# RTI-RoR.net
KiCad netlist of a schematic drawn in EAGLE
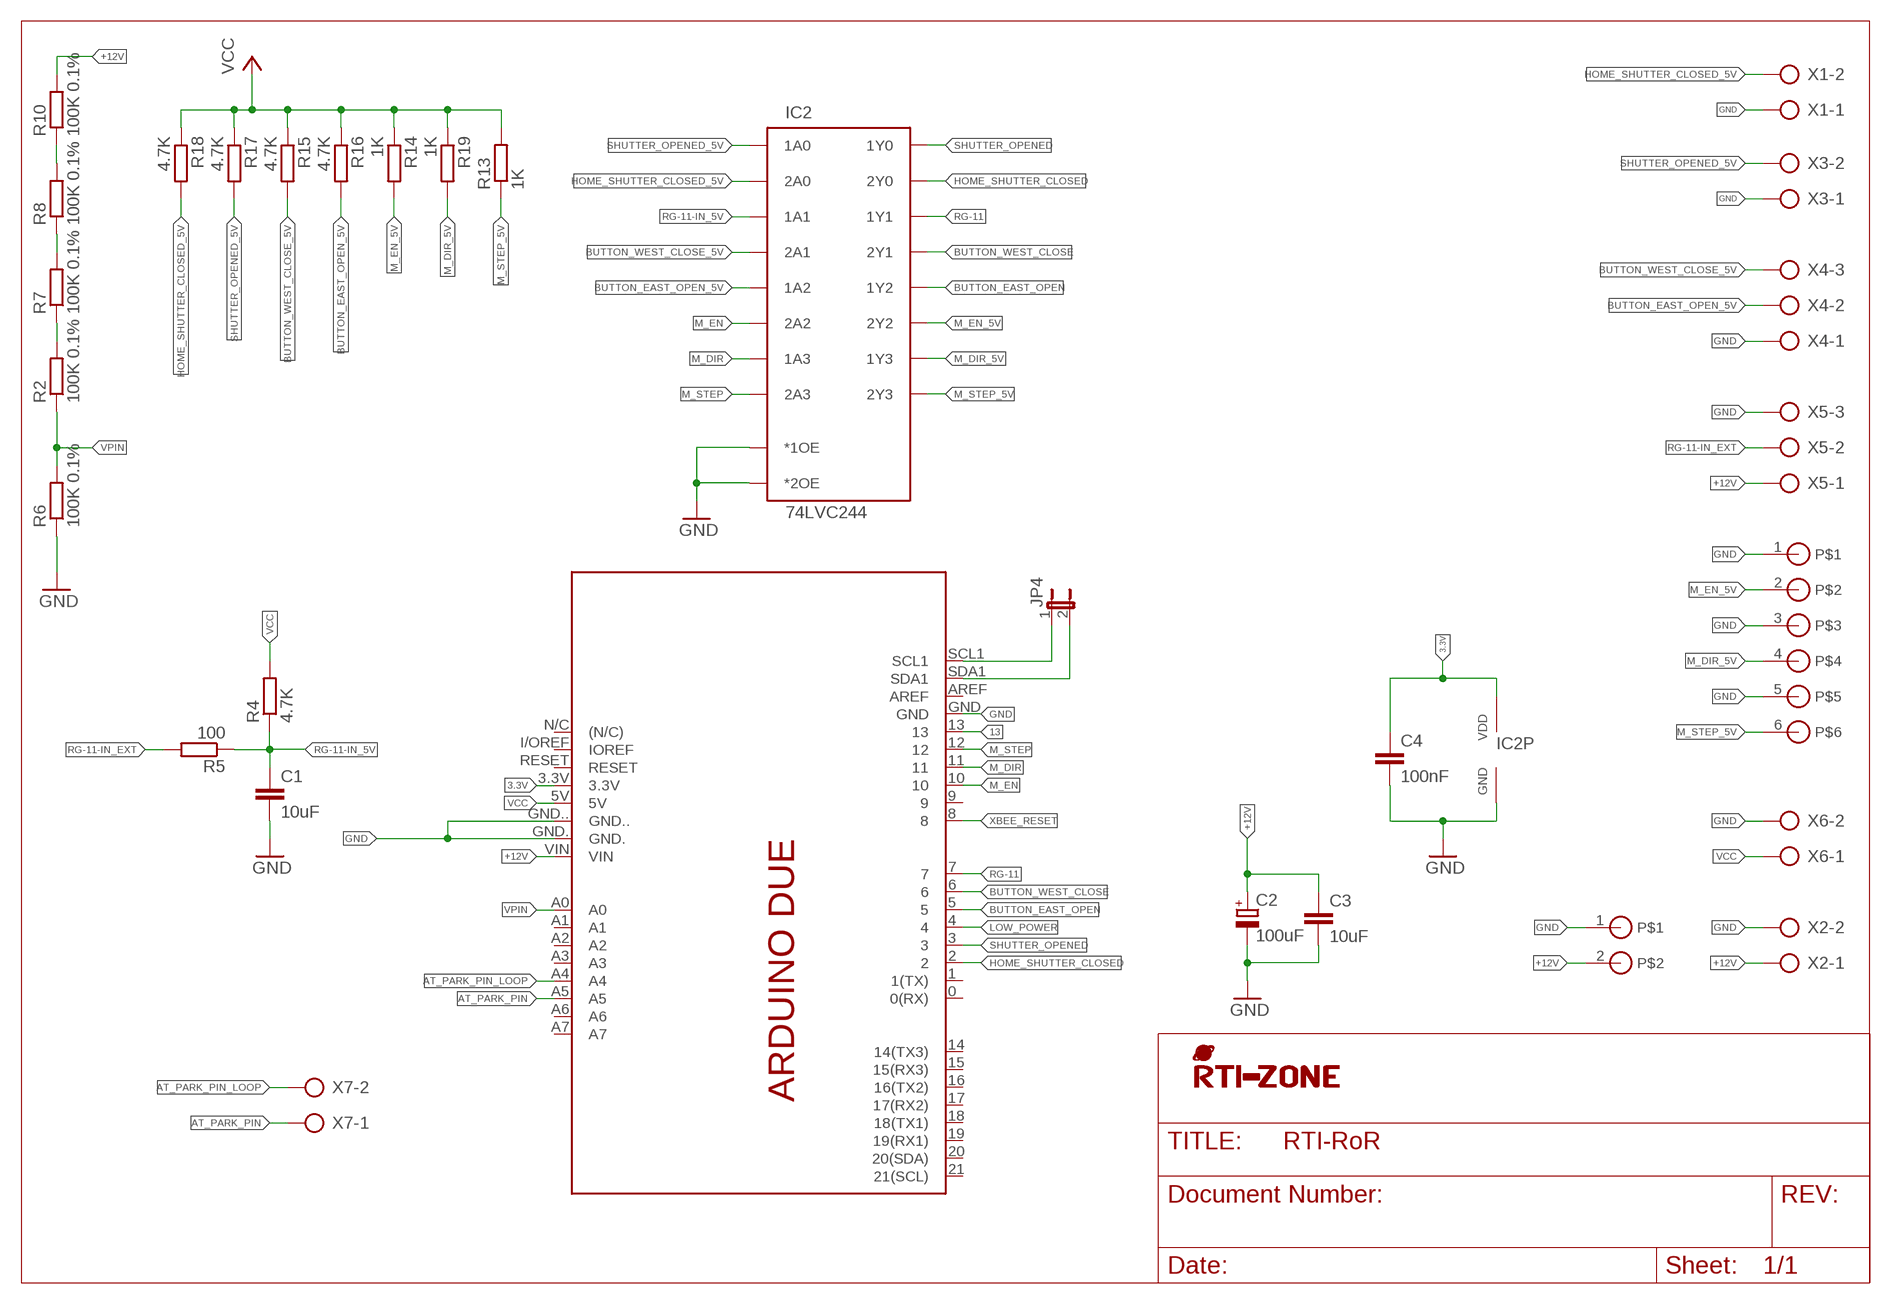
[diagram p0: schematic, sheet 1]

(export (version "E")
  (design (tool "Eeschema 10.0.6"))
  (components
    (comp (ref "C1")
      (value "10uF")
      (footprint "eagle-import:C0805")
      (libsource (lib "eagle-import") (part "C-EU'0805'"))
    )
    (comp (ref "C2")
      (value "100uF")
      (footprint "eagle-import:UD-10X10_NICHICON")
      (libsource (lib "eagle-import") (part "CPOL-EU"))
    )
    (comp (ref "C3")
      (value "10uF")
      (footprint "eagle-import:C0805")
      (libsource (lib "eagle-import") (part "C-EU'0805'"))
    )
    (comp (ref "C4")
      (value "100nF")
      (footprint "eagle-import:C0805")
      (libsource (lib "eagle-import") (part "C-EU'0805'"))
    )
    (comp (ref "IC2")
      (value "74LVC244")
      (footprint "eagle-import:TSSOP20")
      (libsource (lib "eagle-import") (part "74244LVC"))
    )
    (comp (ref "JP4")
      (value "JP1E")
      (footprint "eagle-import:JP1")
      (libsource (lib "eagle-import") (part "JP1E"))
    )
    (comp (ref "PCB1")
      (value "ARDUINO_DUE_SHIELD_SHORT")
      (footprint "eagle-import:ARDUINO_DUE_SHIELD_SHORT")
      (libsource (lib "eagle-import") (part "ARDUINO_DUE_SHIELD_SHORT"))
    )
    (comp (ref "R2")
      (value "100K 0.1%")
      (footprint "eagle-import:R0805")
      (libsource (lib "eagle-import") (part "R-EU'0805'"))
    )
    (comp (ref "R4")
      (value "4.7K")
      (footprint "eagle-import:R0805")
      (libsource (lib "eagle-import") (part "R-EU'0805'"))
    )
    (comp (ref "R5")
      (value "100")
      (footprint "eagle-import:R0805")
      (libsource (lib "eagle-import") (part "R-EU'0805'"))
    )
    (comp (ref "R6")
      (value "100K 0.1%")
      (footprint "eagle-import:R0805")
      (libsource (lib "eagle-import") (part "R-EU'0805'"))
    )
    (comp (ref "R7")
      (value "100K 0.1%")
      (footprint "eagle-import:R0805")
      (libsource (lib "eagle-import") (part "R-EU'0805'"))
    )
    (comp (ref "R8")
      (value "100K 0.1%")
      (footprint "eagle-import:R0805")
      (libsource (lib "eagle-import") (part "R-EU'0805'"))
    )
    (comp (ref "R10")
      (value "100K 0.1%")
      (footprint "eagle-import:R0805")
      (libsource (lib "eagle-import") (part "R-EU'0805'"))
    )
    (comp (ref "R13")
      (value "1K")
      (footprint "eagle-import:R0805")
      (libsource (lib "eagle-import") (part "R-EU'0805'"))
    )
    (comp (ref "R14")
      (value "1K")
      (footprint "eagle-import:R0805")
      (libsource (lib "eagle-import") (part "R-EU'0805'"))
    )
    (comp (ref "R15")
      (value "4.7K")
      (footprint "eagle-import:R0805")
      (libsource (lib "eagle-import") (part "R-EU'0805'"))
    )
    (comp (ref "R16")
      (value "4.7K")
      (footprint "eagle-import:R0805")
      (libsource (lib "eagle-import") (part "R-EU'0805'"))
    )
    (comp (ref "R17")
      (value "4.7K")
      (footprint "eagle-import:R0805")
      (libsource (lib "eagle-import") (part "R-EU'0805'"))
    )
    (comp (ref "R18")
      (value "4.7K")
      (footprint "eagle-import:R0805")
      (libsource (lib "eagle-import") (part "R-EU'0805'"))
    )
    (comp (ref "R19")
      (value "1K")
      (footprint "eagle-import:R0805")
      (libsource (lib "eagle-import") (part "R-EU'0805'"))
    )
    (comp (ref "U$2")
      (value "STL-140-2")
      (footprint "eagle-import:STL-140-2")
      (libsource (lib "eagle-import") (part "STL-140-2"))
    )
    (comp (ref "U$3")
      (value "STL-140-6")
      (footprint "eagle-import:STL-140-6")
      (libsource (lib "eagle-import") (part "STL-140-6"))
    )
    (comp (ref "U$4")
      (value "RTI-LOGO_BIG")
      (footprint "eagle-import:LOGO_BIG")
      (libsource (lib "eagle-import") (part "RTI-LOGO_BIG"))
    )
    (comp (ref "X1")
      (value "AK500/2")
      (footprint "eagle-import:AK500_2")
      (libsource (lib "eagle-import") (part "AK500/2"))
    )
    (comp (ref "X2")
      (value "AK500/2")
      (footprint "eagle-import:AK500_2")
      (libsource (lib "eagle-import") (part "AK500/2"))
    )
    (comp (ref "X3")
      (value "AK500/2")
      (footprint "eagle-import:AK500_2")
      (libsource (lib "eagle-import") (part "AK500/2"))
    )
    (comp (ref "X4")
      (value "AK500/3")
      (footprint "eagle-import:AK500_3")
      (libsource (lib "eagle-import") (part "AK500/3"))
    )
    (comp (ref "X5")
      (value "AK500/3")
      (footprint "eagle-import:AK500_3")
      (libsource (lib "eagle-import") (part "AK500/3"))
    )
    (comp (ref "X6")
      (value "AK500/2")
      (footprint "eagle-import:AK500_2")
      (libsource (lib "eagle-import") (part "AK500/2"))
    )
    (comp (ref "X7")
      (value "AK500/2")
      (footprint "eagle-import:AK500_2")
      (libsource (lib "eagle-import") (part "AK500/2"))
    )
  )
  (nets
    (net (code "1") (name "+12V") (class "Default")
      (node (ref "C2") (pin "+") (pinfunction "+_+") (pintype "passive"))
      (node (ref "C3") (pin "1") (pinfunction "1_1") (pintype "passive"))
      (node (ref "PCB1") (pin "VIN") (pinfunction "VIN_VIN") (pintype "bidirectional"))
      (node (ref "R10") (pin "2") (pinfunction "2_2") (pintype "passive"))
      (node (ref "U$2") (pin "2") (pinfunction "P$2_2") (pintype "bidirectional"))
      (node (ref "X2") (pin "1") (pinfunction "KL_1") (pintype "passive"))
      (node (ref "X5") (pin "1") (pinfunction "KL_1") (pintype "passive"))
    )
    (net (code "2") (name "3.3V") (class "Default")
      (node (ref "C4") (pin "1") (pinfunction "1_1") (pintype "passive"))
      (node (ref "IC2") (pin "P$20") (pinfunction "VDD_P$20") (pintype "power_in"))
      (node (ref "PCB1") (pin "3.3V") (pinfunction "3.3V_3.3V") (pintype "bidirectional"))
    )
    (net (code "3") (name "13") (class "Default")
      (node (ref "PCB1") (pin "13") (pinfunction "13_13") (pintype "bidirectional"))
    )
    (net (code "4") (name "AT_PARK_PIN") (class "Default")
      (node (ref "PCB1") (pin "A5") (pinfunction "A5_A5") (pintype "bidirectional"))
      (node (ref "X7") (pin "1") (pinfunction "KL_1") (pintype "passive"))
    )
    (net (code "5") (name "AT_PARK_PIN_LOOP") (class "Default")
      (node (ref "PCB1") (pin "A4") (pinfunction "A4_A4") (pintype "bidirectional"))
      (node (ref "X7") (pin "2") (pinfunction "KL_2") (pintype "passive"))
    )
    (net (code "6") (name "BUTTON_EAST_OPEN") (class "Default")
      (node (ref "IC2") (pin "P$14") (pinfunction "1Y2_P$14") (pintype "output"))
      (node (ref "PCB1") (pin "5") (pinfunction "5_5") (pintype "bidirectional"))
    )
    (net (code "7") (name "BUTTON_EAST_OPEN_5V") (class "Default")
      (node (ref "IC2") (pin "P$6") (pinfunction "1A2_P$6") (pintype "input"))
      (node (ref "R16") (pin "2") (pinfunction "2_2") (pintype "passive"))
      (node (ref "X4") (pin "2") (pinfunction "KL_2") (pintype "passive"))
    )
    (net (code "8") (name "BUTTON_WEST_CLOSE") (class "Default")
      (node (ref "IC2") (pin "P$5") (pinfunction "2Y1_P$5") (pintype "output"))
      (node (ref "PCB1") (pin "6") (pinfunction "6_6") (pintype "bidirectional"))
    )
    (net (code "9") (name "BUTTON_WEST_CLOSE_5V") (class "Default")
      (node (ref "IC2") (pin "P$15") (pinfunction "2A1_P$15") (pintype "input"))
      (node (ref "R15") (pin "2") (pinfunction "2_2") (pintype "passive"))
      (node (ref "X4") (pin "3") (pinfunction "KL_3") (pintype "passive"))
    )
    (net (code "10") (name "GND") (class "Default")
      (node (ref "C1") (pin "2") (pinfunction "2_2") (pintype "passive"))
      (node (ref "C2") (pin "-") (pinfunction "-_-") (pintype "passive"))
      (node (ref "C3") (pin "2") (pinfunction "2_2") (pintype "passive"))
      (node (ref "C4") (pin "2") (pinfunction "2_2") (pintype "passive"))
      (node (ref "IC2") (pin "P$1") (pinfunction "*1OE_P$1") (pintype "input"))
      (node (ref "IC2") (pin "P$10") (pinfunction "GND_P$10") (pintype "power_in"))
      (node (ref "IC2") (pin "P$19") (pinfunction "*2OE_P$19") (pintype "input"))
      (node (ref "PCB1") (pin "GND") (pinfunction "GND_GND") (pintype "bidirectional"))
      (node (ref "PCB1") (pin "GND.") (pinfunction "GND._GND.") (pintype "bidirectional"))
      (node (ref "PCB1") (pin "GND..") (pinfunction "GND.._GND..") (pintype "bidirectional"))
      (node (ref "R6") (pin "1") (pinfunction "1_1") (pintype "passive"))
      (node (ref "U$2") (pin "1") (pinfunction "P$1_1") (pintype "bidirectional"))
      (node (ref "U$3") (pin "1") (pinfunction "P$1_1") (pintype "bidirectional"))
      (node (ref "U$3") (pin "3") (pinfunction "P$3_3") (pintype "bidirectional"))
      (node (ref "U$3") (pin "5") (pinfunction "P$5_5") (pintype "bidirectional"))
      (node (ref "X1") (pin "1") (pinfunction "KL_1") (pintype "passive"))
      (node (ref "X2") (pin "2") (pinfunction "KL_2") (pintype "passive"))
      (node (ref "X3") (pin "1") (pinfunction "KL_1") (pintype "passive"))
      (node (ref "X4") (pin "1") (pinfunction "KL_1") (pintype "passive"))
      (node (ref "X5") (pin "3") (pinfunction "KL_3") (pintype "passive"))
      (node (ref "X6") (pin "2") (pinfunction "KL_2") (pintype "passive"))
    )
    (net (code "11") (name "HOME_SHUTTER_CLOSED") (class "Default")
      (node (ref "IC2") (pin "P$3") (pinfunction "2Y0_P$3") (pintype "output"))
      (node (ref "PCB1") (pin "2") (pinfunction "2_2") (pintype "bidirectional"))
    )
    (net (code "12") (name "HOME_SHUTTER_CLOSED_5V") (class "Default")
      (node (ref "IC2") (pin "P$17") (pinfunction "2A0_P$17") (pintype "input"))
      (node (ref "R18") (pin "2") (pinfunction "2_2") (pintype "passive"))
      (node (ref "X1") (pin "2") (pinfunction "KL_2") (pintype "passive"))
    )
    (net (code "13") (name "LOW_POWER") (class "Default")
      (node (ref "PCB1") (pin "4") (pinfunction "4_4") (pintype "bidirectional"))
    )
    (net (code "14") (name "M_DIR") (class "Default")
      (node (ref "IC2") (pin "P$8") (pinfunction "1A3_P$8") (pintype "input"))
      (node (ref "PCB1") (pin "11") (pinfunction "11_11") (pintype "bidirectional"))
    )
    (net (code "15") (name "M_DIR_5V") (class "Default")
      (node (ref "IC2") (pin "P$12") (pinfunction "1Y3_P$12") (pintype "output"))
      (node (ref "R19") (pin "2") (pinfunction "2_2") (pintype "passive"))
      (node (ref "U$3") (pin "4") (pinfunction "P$4_4") (pintype "bidirectional"))
    )
    (net (code "16") (name "M_EN") (class "Default")
      (node (ref "IC2") (pin "P$13") (pinfunction "2A2_P$13") (pintype "input"))
      (node (ref "PCB1") (pin "10") (pinfunction "10_10") (pintype "bidirectional"))
    )
    (net (code "17") (name "M_EN_5V") (class "Default")
      (node (ref "IC2") (pin "P$7") (pinfunction "2Y2_P$7") (pintype "output"))
      (node (ref "R14") (pin "2") (pinfunction "2_2") (pintype "passive"))
      (node (ref "U$3") (pin "2") (pinfunction "P$2_2") (pintype "bidirectional"))
    )
    (net (code "18") (name "M_STEP") (class "Default")
      (node (ref "IC2") (pin "P$11") (pinfunction "2A3_P$11") (pintype "input"))
      (node (ref "PCB1") (pin "12") (pinfunction "12_12") (pintype "bidirectional"))
    )
    (net (code "19") (name "M_STEP_5V") (class "Default")
      (node (ref "IC2") (pin "P$9") (pinfunction "2Y3_P$9") (pintype "output"))
      (node (ref "R13") (pin "1") (pinfunction "1_1") (pintype "passive"))
      (node (ref "U$3") (pin "6") (pinfunction "P$6_6") (pintype "bidirectional"))
    )
    (net (code "20") (name "Net-(JP4-Pad1)") (class "Default")
      (node (ref "JP4") (pin "1") (pinfunction "1_1") (pintype "passive"))
      (node (ref "PCB1") (pin "SCL1") (pinfunction "SCL1_SCL1") (pintype "bidirectional"))
    )
    (net (code "21") (name "Net-(JP4-Pad2)") (class "Default")
      (node (ref "JP4") (pin "2") (pinfunction "2_2") (pintype "passive"))
      (node (ref "PCB1") (pin "SDA1") (pinfunction "SDA1_SDA1") (pintype "bidirectional"))
    )
    (net (code "22") (name "Net-(R2-Pad2)") (class "Default")
      (node (ref "R2") (pin "2") (pinfunction "2_2") (pintype "passive"))
      (node (ref "R7") (pin "1") (pinfunction "1_1") (pintype "passive"))
    )
    (net (code "23") (name "Net-(R7-Pad2)") (class "Default")
      (node (ref "R7") (pin "2") (pinfunction "2_2") (pintype "passive"))
      (node (ref "R8") (pin "1") (pinfunction "1_1") (pintype "passive"))
    )
    (net (code "24") (name "Net-(R10-Pad1)") (class "Default")
      (node (ref "R10") (pin "1") (pinfunction "1_1") (pintype "passive"))
      (node (ref "R8") (pin "2") (pinfunction "2_2") (pintype "passive"))
    )
    (net (code "25") (name "RG-11") (class "Default")
      (node (ref "IC2") (pin "P$16") (pinfunction "1Y1_P$16") (pintype "output"))
      (node (ref "PCB1") (pin "7") (pinfunction "7_7") (pintype "bidirectional"))
    )
    (net (code "26") (name "RG-11-IN_5V") (class "Default")
      (node (ref "C1") (pin "1") (pinfunction "1_1") (pintype "passive"))
      (node (ref "IC2") (pin "P$4") (pinfunction "1A1_P$4") (pintype "input"))
      (node (ref "R4") (pin "1") (pinfunction "1_1") (pintype "passive"))
      (node (ref "R5") (pin "1") (pinfunction "1_1") (pintype "passive"))
    )
    (net (code "27") (name "RG-11-IN_EXT") (class "Default")
      (node (ref "R5") (pin "2") (pinfunction "2_2") (pintype "passive"))
      (node (ref "X5") (pin "2") (pinfunction "KL_2") (pintype "passive"))
    )
    (net (code "28") (name "SHUTTER_OPENED") (class "Default")
      (node (ref "IC2") (pin "P$18") (pinfunction "1Y0_P$18") (pintype "output"))
      (node (ref "PCB1") (pin "3") (pinfunction "3_3") (pintype "bidirectional"))
    )
    (net (code "29") (name "SHUTTER_OPENED_5V") (class "Default")
      (node (ref "IC2") (pin "P$2") (pinfunction "1A0_P$2") (pintype "input"))
      (node (ref "R17") (pin "2") (pinfunction "2_2") (pintype "passive"))
      (node (ref "X3") (pin "2") (pinfunction "KL_2") (pintype "passive"))
    )
    (net (code "30") (name "VCC") (class "Default")
      (node (ref "PCB1") (pin "5V") (pinfunction "5V_5V") (pintype "bidirectional"))
      (node (ref "R13") (pin "2") (pinfunction "2_2") (pintype "passive"))
      (node (ref "R14") (pin "1") (pinfunction "1_1") (pintype "passive"))
      (node (ref "R15") (pin "1") (pinfunction "1_1") (pintype "passive"))
      (node (ref "R16") (pin "1") (pinfunction "1_1") (pintype "passive"))
      (node (ref "R17") (pin "1") (pinfunction "1_1") (pintype "passive"))
      (node (ref "R18") (pin "1") (pinfunction "1_1") (pintype "passive"))
      (node (ref "R19") (pin "1") (pinfunction "1_1") (pintype "passive"))
      (node (ref "R4") (pin "2") (pinfunction "2_2") (pintype "passive"))
      (node (ref "X6") (pin "1") (pinfunction "KL_1") (pintype "passive"))
    )
    (net (code "31") (name "VPIN") (class "Default")
      (node (ref "PCB1") (pin "A0") (pinfunction "A0_A0") (pintype "bidirectional"))
      (node (ref "R2") (pin "1") (pinfunction "1_1") (pintype "passive"))
      (node (ref "R6") (pin "2") (pinfunction "2_2") (pintype "passive"))
    )
    (net (code "32") (name "XBEE_RESET") (class "Default")
      (node (ref "PCB1") (pin "8") (pinfunction "8_8") (pintype "bidirectional"))
    )
    (net (code "33") (name "unconnected-(PCB1-(N{slash}C)-PadN{slash}C)") (class "Default")
      (node (ref "PCB1") (pin "N/C") (pinfunction "(N/C)_N/C") (pintype "bidirectional"))
    )
    (net (code "34") (name "unconnected-(PCB1-0(RX)-Pad0)") (class "Default")
      (node (ref "PCB1") (pin "0") (pinfunction "0(RX)_0") (pintype "bidirectional"))
    )
    (net (code "35") (name "unconnected-(PCB1-1(TX)-Pad1)") (class "Default")
      (node (ref "PCB1") (pin "1") (pinfunction "1(TX)_1") (pintype "bidirectional"))
    )
    (net (code "36") (name "unconnected-(PCB1-14(TX3)-Pad14)") (class "Default")
      (node (ref "PCB1") (pin "14") (pinfunction "14(TX3)_14") (pintype "bidirectional"))
    )
    (net (code "37") (name "unconnected-(PCB1-15(RX3)-Pad15)") (class "Default")
      (node (ref "PCB1") (pin "15") (pinfunction "15(RX3)_15") (pintype "bidirectional"))
    )
    (net (code "38") (name "unconnected-(PCB1-16(TX2)-Pad16)") (class "Default")
      (node (ref "PCB1") (pin "16") (pinfunction "16(TX2)_16") (pintype "bidirectional"))
    )
    (net (code "39") (name "unconnected-(PCB1-17(RX2)-Pad17)") (class "Default")
      (node (ref "PCB1") (pin "17") (pinfunction "17(RX2)_17") (pintype "bidirectional"))
    )
    (net (code "40") (name "unconnected-(PCB1-18(TX1)-Pad18)") (class "Default")
      (node (ref "PCB1") (pin "18") (pinfunction "18(TX1)_18") (pintype "bidirectional"))
    )
    (net (code "41") (name "unconnected-(PCB1-19(RX1)-Pad19)") (class "Default")
      (node (ref "PCB1") (pin "19") (pinfunction "19(RX1)_19") (pintype "bidirectional"))
    )
    (net (code "42") (name "unconnected-(PCB1-20(SDA)-Pad20)") (class "Default")
      (node (ref "PCB1") (pin "20") (pinfunction "20(SDA)_20") (pintype "bidirectional"))
    )
    (net (code "43") (name "unconnected-(PCB1-21(SCL)-Pad21)") (class "Default")
      (node (ref "PCB1") (pin "21") (pinfunction "21(SCL)_21") (pintype "bidirectional"))
    )
    (net (code "44") (name "unconnected-(PCB1-IOREF-PadI{slash}OREF)") (class "Default")
      (node (ref "PCB1") (pin "I/OREF") (pinfunction "IOREF_I/OREF") (pintype "bidirectional"))
    )
    (net (code "45") (name "unconnected-(PCB1-Pad9)") (class "Default")
      (node (ref "PCB1") (pin "9") (pinfunction "9_9") (pintype "bidirectional"))
    )
    (net (code "46") (name "unconnected-(PCB1-PadA1)") (class "Default")
      (node (ref "PCB1") (pin "A1") (pinfunction "A1_A1") (pintype "bidirectional"))
    )
    (net (code "47") (name "unconnected-(PCB1-PadA2)") (class "Default")
      (node (ref "PCB1") (pin "A2") (pinfunction "A2_A2") (pintype "bidirectional"))
    )
    (net (code "48") (name "unconnected-(PCB1-PadA3)") (class "Default")
      (node (ref "PCB1") (pin "A3") (pinfunction "A3_A3") (pintype "bidirectional"))
    )
    (net (code "49") (name "unconnected-(PCB1-PadA6)") (class "Default")
      (node (ref "PCB1") (pin "A6") (pinfunction "A6_A6") (pintype "bidirectional"))
    )
    (net (code "50") (name "unconnected-(PCB1-PadA7)") (class "Default")
      (node (ref "PCB1") (pin "A7") (pinfunction "A7_A7") (pintype "bidirectional"))
    )
    (net (code "51") (name "unconnected-(PCB1-PadAREF)") (class "Default")
      (node (ref "PCB1") (pin "AREF") (pinfunction "AREF_AREF") (pintype "bidirectional"))
    )
    (net (code "52") (name "unconnected-(PCB1-PadRESET)") (class "Default")
      (node (ref "PCB1") (pin "RESET") (pinfunction "RESET_RESET") (pintype "bidirectional"))
    )
  )
)
